# DRV10987.net
KiCad netlist of a schematic drawn in EAGLE
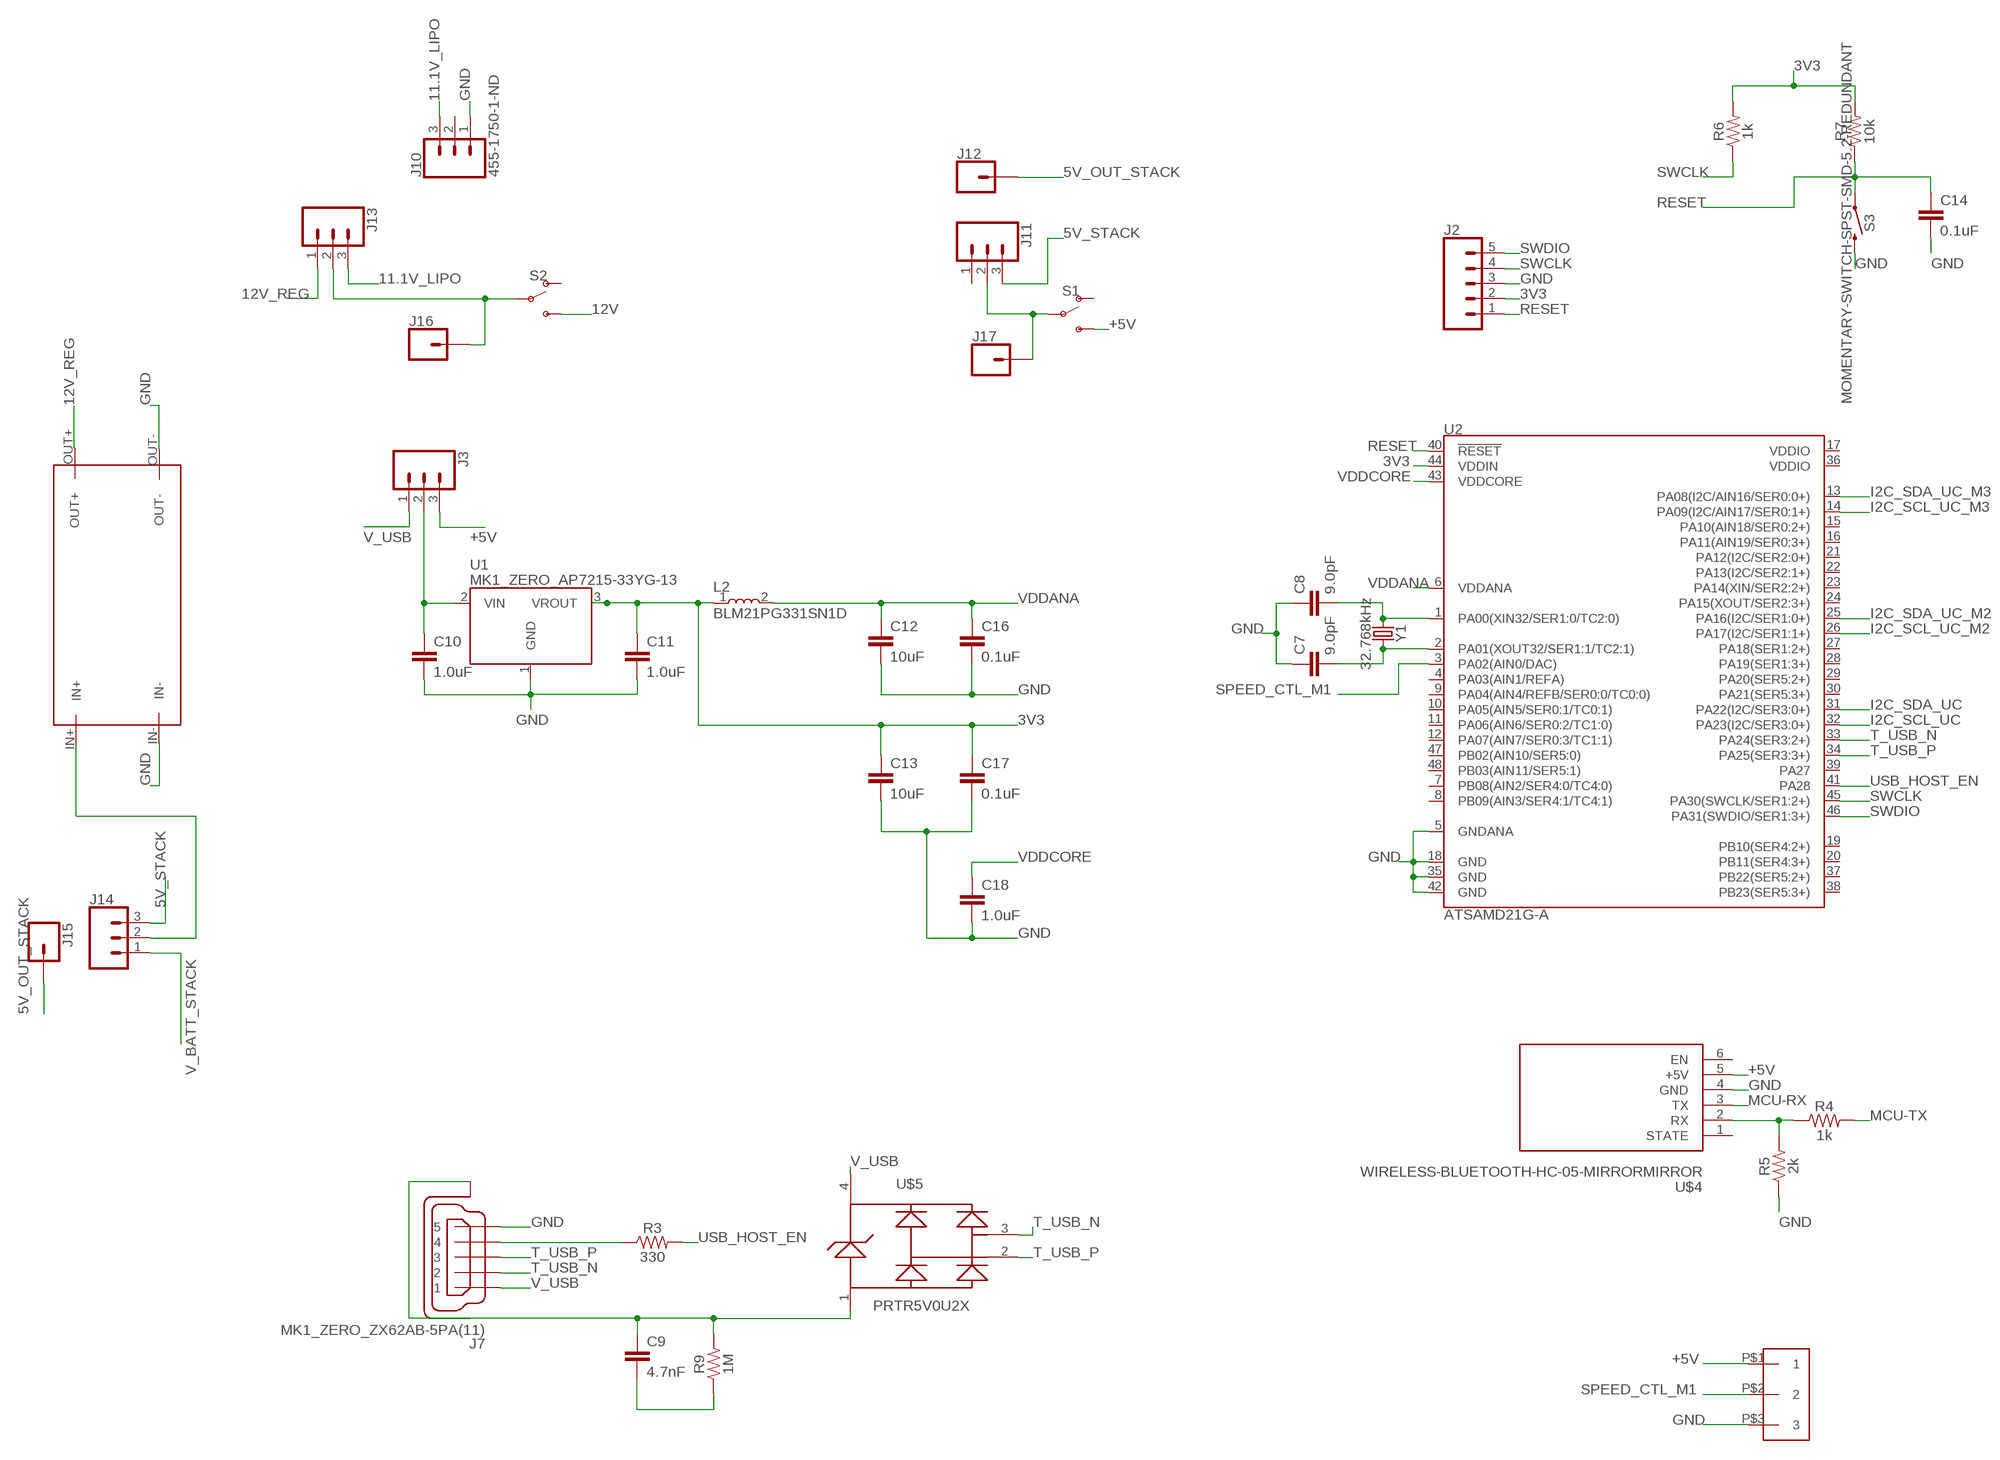
[diagram p0: schematic, sheet 1, part 1 of 2]
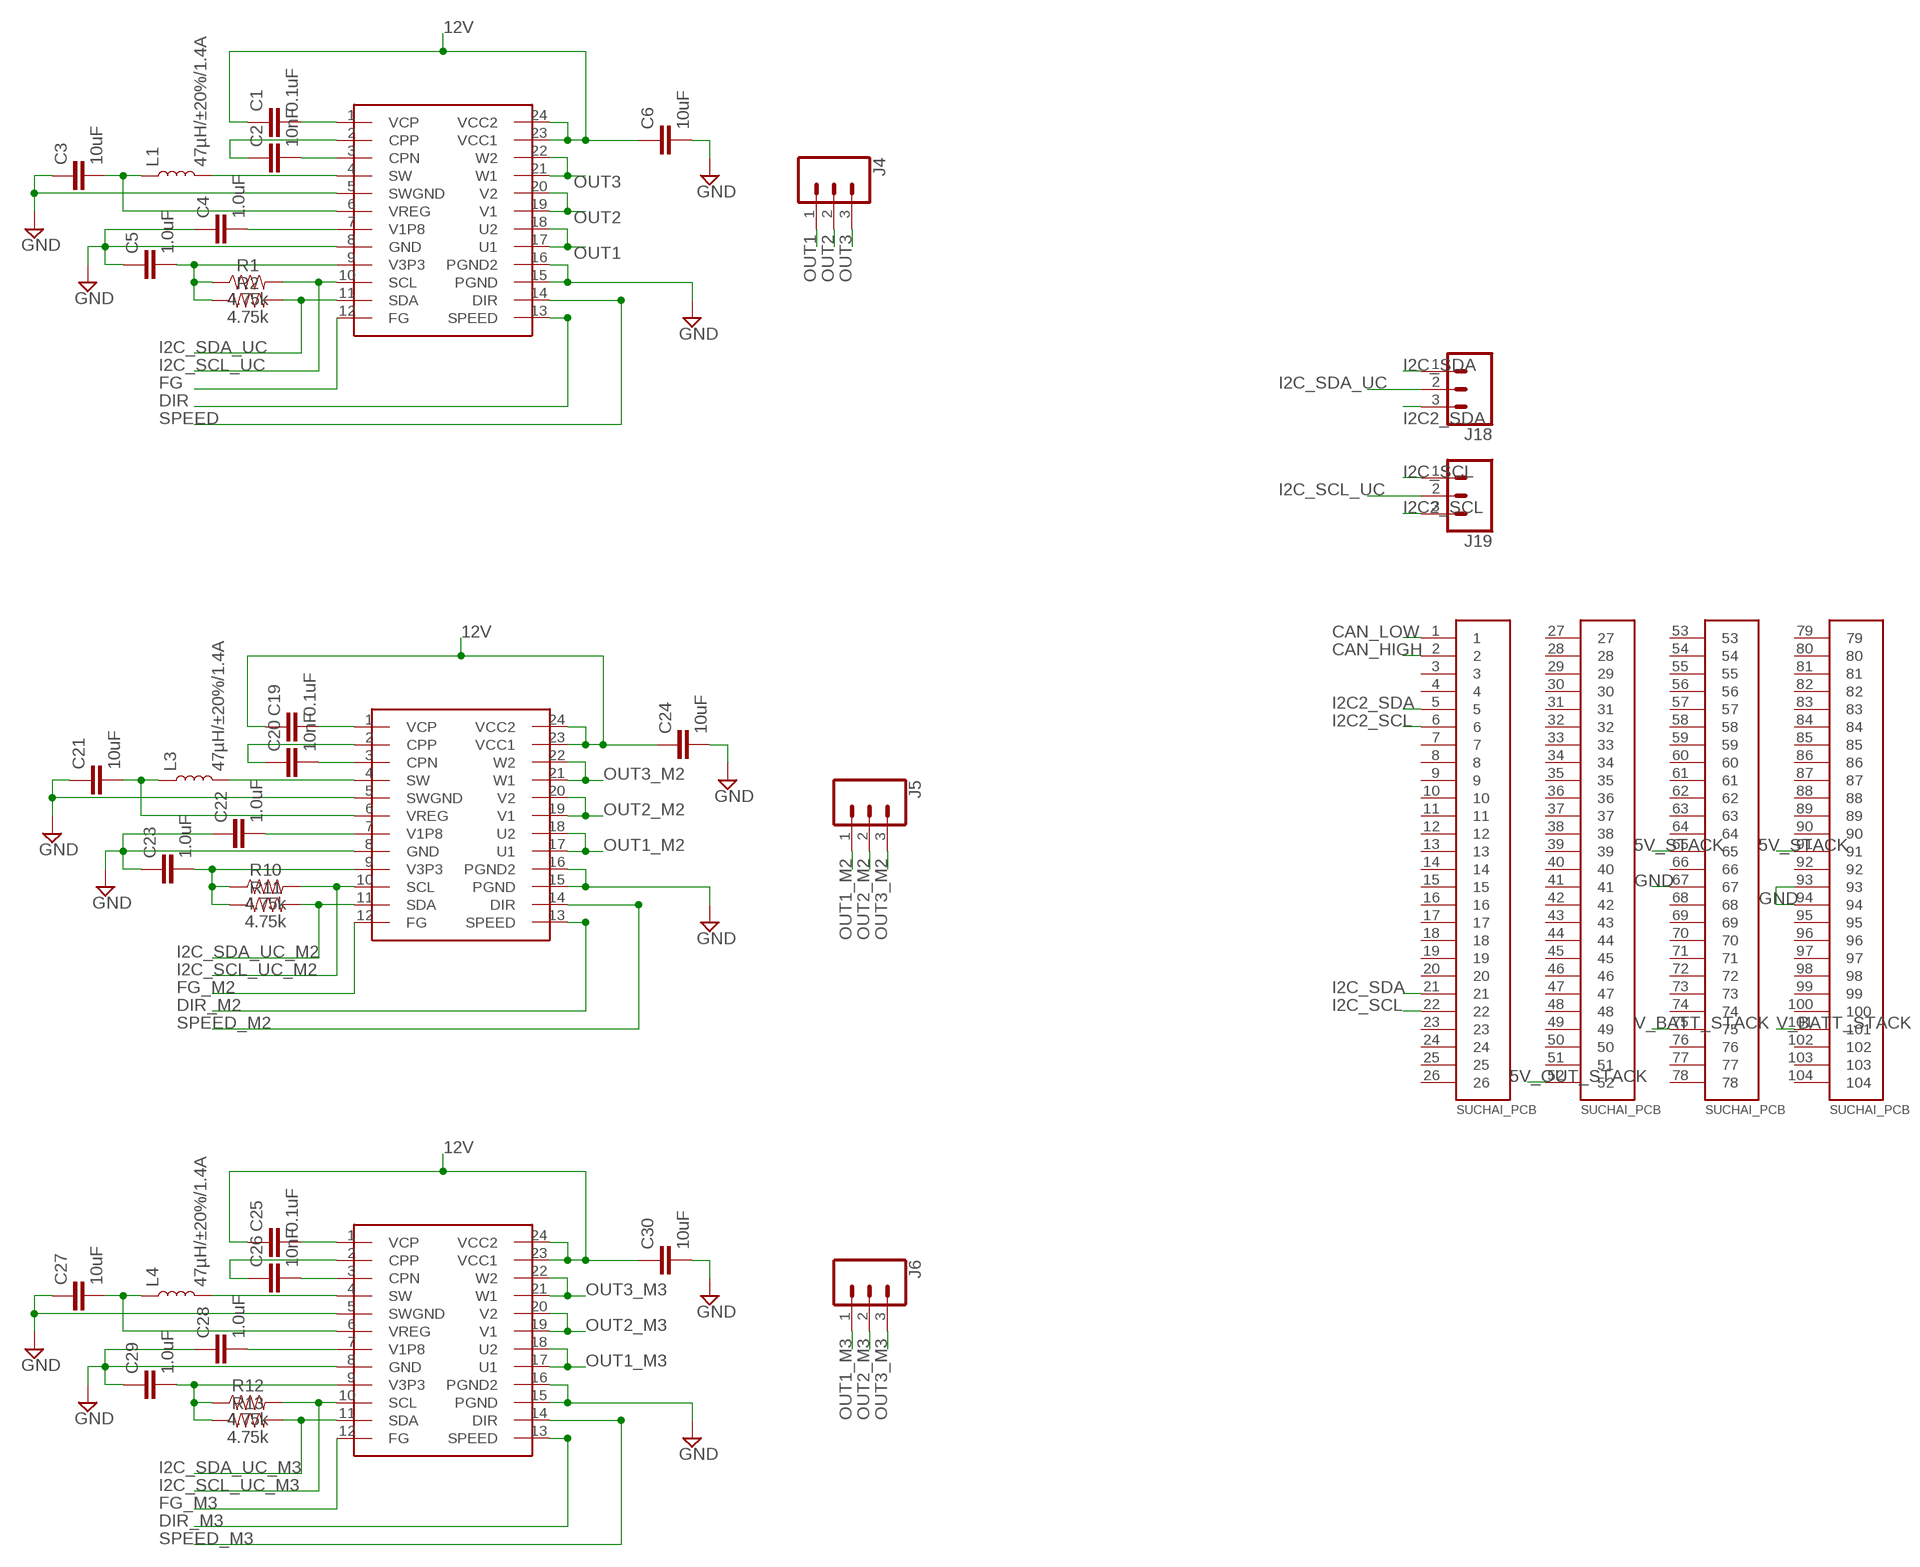
[diagram p1: schematic, sheet 1, part 2 of 2]

(export (version "E")
  (design (tool "Eeschema 10.0.6"))
  (components
    (comp (ref "C1")
      (value "0.1uF")
      (footprint "eagle-import:0805")
      (libsource (lib "eagle-import") (part "1.0UF-0805-25V-10%"))
    )
    (comp (ref "C2")
      (value "10nF")
      (footprint "eagle-import:0805")
      (libsource (lib "eagle-import") (part "1.0UF-0805-25V-10%"))
    )
    (comp (ref "C3")
      (value "10uF")
      (footprint "eagle-import:0805")
      (libsource (lib "eagle-import") (part "1.0UF-0805-25V-10%"))
    )
    (comp (ref "C4")
      (value "1.0uF")
      (footprint "eagle-import:0805")
      (libsource (lib "eagle-import") (part "1.0UF-0805-25V-10%"))
    )
    (comp (ref "C5")
      (value "1.0uF")
      (footprint "eagle-import:0805")
      (libsource (lib "eagle-import") (part "1.0UF-0805-25V-10%"))
    )
    (comp (ref "C6")
      (value "10uF")
      (footprint "eagle-import:0805")
      (libsource (lib "eagle-import") (part "1.0UF-0805-25V-10%"))
    )
    (comp (ref "C7")
      (value "9.0pF")
      (footprint "eagle-import:0603")
      (libsource (lib "eagle-import") (part "9.0PF-0603-50V-10%"))
    )
    (comp (ref "C8")
      (value "9.0pF")
      (footprint "eagle-import:0603")
      (libsource (lib "eagle-import") (part "9.0PF-0603-50V-10%"))
    )
    (comp (ref "C9")
      (value "4.7nF")
      (footprint "eagle-import:0603")
      (libsource (lib "eagle-import") (part "4.7PF-0603-50V-5%"))
    )
    (comp (ref "C10")
      (value "1.0uF")
      (footprint "eagle-import:0805")
      (libsource (lib "eagle-import") (part "1.0UF-0805-25V-(+80/-20%)"))
    )
    (comp (ref "C11")
      (value "1.0uF")
      (footprint "eagle-import:0805")
      (libsource (lib "eagle-import") (part "1.0UF-0805-25V-(+80/-20%)"))
    )
    (comp (ref "C12")
      (value "10uF")
      (footprint "eagle-import:0805")
      (libsource (lib "eagle-import") (part "10UF-0805-10V-10%"))
    )
    (comp (ref "C13")
      (value "10uF")
      (footprint "eagle-import:0805")
      (libsource (lib "eagle-import") (part "10UF-0805-10V-10%"))
    )
    (comp (ref "C14")
      (value "0.1uF")
      (footprint "eagle-import:0805")
      (libsource (lib "eagle-import") (part "1.0UF-0805-25V-(+80/-20%)"))
    )
    (comp (ref "C16")
      (value "0.1uF")
      (footprint "eagle-import:0805")
      (libsource (lib "eagle-import") (part "1.0UF-0805-25V-(+80/-20%)"))
    )
    (comp (ref "C17")
      (value "0.1uF")
      (footprint "eagle-import:0805")
      (libsource (lib "eagle-import") (part "1.0UF-0805-25V-(+80/-20%)"))
    )
    (comp (ref "C18")
      (value "1.0uF")
      (footprint "eagle-import:0805")
      (libsource (lib "eagle-import") (part "1.0UF-0805-25V-(+80/-20%)"))
    )
    (comp (ref "C19")
      (value "0.1uF")
      (footprint "eagle-import:0805")
      (libsource (lib "eagle-import") (part "1.0UF-0805-25V-10%"))
    )
    (comp (ref "C20")
      (value "10nF")
      (footprint "eagle-import:0805")
      (libsource (lib "eagle-import") (part "1.0UF-0805-25V-10%"))
    )
    (comp (ref "C21")
      (value "10uF")
      (footprint "eagle-import:0805")
      (libsource (lib "eagle-import") (part "1.0UF-0805-25V-10%"))
    )
    (comp (ref "C22")
      (value "1.0uF")
      (footprint "eagle-import:0805")
      (libsource (lib "eagle-import") (part "1.0UF-0805-25V-10%"))
    )
    (comp (ref "C23")
      (value "1.0uF")
      (footprint "eagle-import:0805")
      (libsource (lib "eagle-import") (part "1.0UF-0805-25V-10%"))
    )
    (comp (ref "C24")
      (value "10uF")
      (footprint "eagle-import:0805")
      (libsource (lib "eagle-import") (part "1.0UF-0805-25V-10%"))
    )
    (comp (ref "C25")
      (value "0.1uF")
      (footprint "eagle-import:0805")
      (libsource (lib "eagle-import") (part "1.0UF-0805-25V-10%"))
    )
    (comp (ref "C26")
      (value "10nF")
      (footprint "eagle-import:0805")
      (libsource (lib "eagle-import") (part "1.0UF-0805-25V-10%"))
    )
    (comp (ref "C27")
      (value "10uF")
      (footprint "eagle-import:0805")
      (libsource (lib "eagle-import") (part "1.0UF-0805-25V-10%"))
    )
    (comp (ref "C28")
      (value "1.0uF")
      (footprint "eagle-import:0805")
      (libsource (lib "eagle-import") (part "1.0UF-0805-25V-10%"))
    )
    (comp (ref "C29")
      (value "1.0uF")
      (footprint "eagle-import:0805")
      (libsource (lib "eagle-import") (part "1.0UF-0805-25V-10%"))
    )
    (comp (ref "C30")
      (value "10uF")
      (footprint "eagle-import:0805")
      (libsource (lib "eagle-import") (part "1.0UF-0805-25V-10%"))
    )
    (comp (ref "J1")
      (value "SUCHAI_PCB")
      (footprint "eagle-import:SUCHAI_PCB")
      (libsource (lib "eagle-import") (part "SUCHAI_PCB"))
    )
    (comp (ref "J2")
      (value "CONN_05LOCK_LONGPADS")
      (footprint "eagle-import:1X05_LOCK_LONGPADS")
      (libsource (lib "eagle-import") (part "CONN_05LOCK_LONGPADS"))
    )
    (comp (ref "J3")
      (value "CONN_03LOCK_LONGPADS")
      (footprint "eagle-import:1X03_LOCK_LONGPADS")
      (libsource (lib "eagle-import") (part "CONN_03LOCK_LONGPADS"))
    )
    (comp (ref "J4")
      (value "CONN_03LOCK")
      (footprint "eagle-import:1X03_LOCK")
      (libsource (lib "eagle-import") (part "CONN_03LOCK"))
    )
    (comp (ref "J5")
      (value "CONN_03LOCK")
      (footprint "eagle-import:1X03_LOCK")
      (libsource (lib "eagle-import") (part "CONN_03LOCK"))
    )
    (comp (ref "J6")
      (value "CONN_03LOCK")
      (footprint "eagle-import:1X03_LOCK")
      (libsource (lib "eagle-import") (part "CONN_03LOCK"))
    )
    (comp (ref "J7")
      (value "MK1_ZERO_ZX62AB-5PA(11)")
      (footprint "eagle-import:MK1_ZERO_USBMICRO-ZX62-AB-5PA")
      (libsource (lib "eagle-import") (part "MK1_ZERO_ZX62AB-5PA(11)"))
    )
    (comp (ref "J10")
      (value "455-1750-1-ND")
      (footprint "eagle-import:1X03")
      (libsource (lib "eagle-import") (part "CONN_03"))
    )
    (comp (ref "J11")
      (value "CONN_03LOCK")
      (footprint "eagle-import:1X03_LOCK")
      (libsource (lib "eagle-import") (part "CONN_03LOCK"))
    )
    (comp (ref "J12")
      (value "CONN_01")
      (footprint "eagle-import:1X01")
      (libsource (lib "eagle-import") (part "CONN_01"))
    )
    (comp (ref "J13")
      (value "CONN_03LOCK")
      (footprint "eagle-import:1X03_LOCK")
      (libsource (lib "eagle-import") (part "CONN_03LOCK"))
    )
    (comp (ref "J14")
      (value "CONN_03LOCK")
      (footprint "eagle-import:1X03_LOCK")
      (libsource (lib "eagle-import") (part "CONN_03LOCK"))
    )
    (comp (ref "J15")
      (value "CONN_01")
      (footprint "eagle-import:1X01")
      (libsource (lib "eagle-import") (part "CONN_01"))
    )
    (comp (ref "J16")
      (value "CONN_01")
      (footprint "eagle-import:1X01")
      (libsource (lib "eagle-import") (part "CONN_01"))
    )
    (comp (ref "J17")
      (value "CONN_01")
      (footprint "eagle-import:1X01")
      (libsource (lib "eagle-import") (part "CONN_01"))
    )
    (comp (ref "J18")
      (value "CONN_03LOCK")
      (footprint "eagle-import:1X03_LOCK")
      (libsource (lib "eagle-import") (part "CONN_03LOCK"))
    )
    (comp (ref "J19")
      (value "CONN_03LOCK")
      (footprint "eagle-import:1X03_LOCK")
      (libsource (lib "eagle-import") (part "CONN_03LOCK"))
    )
    (comp (ref "L1")
      (value "47µH/±20%/1.4A")
      (footprint "eagle-import:SRN6045")
      (libsource (lib "eagle-import") (part "INDUCTOR-SRN6045-33UH"))
    )
    (comp (ref "L2")
      (value "BLM21PG331SN1D")
      (footprint "eagle-import:INDC2012X87")
      (fields (field (name "MANUFACTURER") "MURATA"))
      (libsource (lib "eagle-import") (part "BLM21PG331SN1D"))
    )
    (comp (ref "L3")
      (value "47µH/±20%/1.4A")
      (footprint "eagle-import:SRN6045")
      (libsource (lib "eagle-import") (part "INDUCTOR-SRN6045-33UH"))
    )
    (comp (ref "L4")
      (value "47µH/±20%/1.4A")
      (footprint "eagle-import:SRN6045")
      (libsource (lib "eagle-import") (part "INDUCTOR-SRN6045-33UH"))
    )
    (comp (ref "R1")
      (value "4.75k")
      (footprint "eagle-import:0805")
      (libsource (lib "eagle-import") (part "RESISTOR0805"))
    )
    (comp (ref "R2")
      (value "4.75k")
      (footprint "eagle-import:0805")
      (libsource (lib "eagle-import") (part "RESISTOR0805"))
    )
    (comp (ref "R3")
      (value "330")
      (footprint "eagle-import:0603")
      (libsource (lib "eagle-import") (part "330OHM-0603-1/10W-1%"))
    )
    (comp (ref "R4")
      (value "1k")
      (footprint "eagle-import:AXIAL-0.3")
      (libsource (lib "eagle-import") (part "resistors-longpads_1KOHM-HORIZ-1/4W-5%"))
    )
    (comp (ref "R5")
      (value "2k")
      (footprint "eagle-import:AXIAL-0.3")
      (libsource (lib "eagle-import") (part "resistors-longpads_RESISTORAXIAL-0.3"))
    )
    (comp (ref "R6")
      (value "1k")
      (footprint "eagle-import:0603")
      (libsource (lib "eagle-import") (part "1KOHM-0603-1/10W-1%"))
    )
    (comp (ref "R7")
      (value "10k")
      (footprint "eagle-import:0603")
      (libsource (lib "eagle-import") (part "10KOHM-0603-1/10W-1%"))
    )
    (comp (ref "R9")
      (value "1M")
      (footprint "eagle-import:0603")
      (libsource (lib "eagle-import") (part "1MOHM-0603-1/4W-5%"))
    )
    (comp (ref "R10")
      (value "4.75k")
      (footprint "eagle-import:0805")
      (libsource (lib "eagle-import") (part "RESISTOR0805"))
    )
    (comp (ref "R11")
      (value "4.75k")
      (footprint "eagle-import:0805")
      (libsource (lib "eagle-import") (part "RESISTOR0805"))
    )
    (comp (ref "R12")
      (value "4.75k")
      (footprint "eagle-import:0805")
      (libsource (lib "eagle-import") (part "RESISTOR0805"))
    )
    (comp (ref "R13")
      (value "4.75k")
      (footprint "eagle-import:0805")
      (libsource (lib "eagle-import") (part "RESISTOR0805"))
    )
    (comp (ref "S1")
      (value "SWITCH-SPDT-PTH-11.6X4.0MM")
      (footprint "eagle-import:SWITCH_SPDT_PTH_11.6X4.0MM")
      (libsource (lib "eagle-import") (part "SWITCH-SPDT-PTH-11.6X4.0MM"))
    )
    (comp (ref "S2")
      (value "SWITCH-SPDT-PTH-11.6X4.0MM")
      (footprint "eagle-import:SWITCH_SPDT_PTH_11.6X4.0MM")
      (libsource (lib "eagle-import") (part "SWITCH-SPDT-PTH-11.6X4.0MM"))
    )
    (comp (ref "S3")
      (value "MOMENTARY-SWITCH-SPST-SMD-5.2-REDUNDANT")
      (footprint "eagle-import:TACTILE_SWITCH_SMD_5.2MM")
      (libsource (lib "eagle-import") (part "MOMENTARY-SWITCH-SPST-SMD-5.2-REDUNDANT"))
    )
    (comp (ref "U$1")
      (value "DRV10987")
      (footprint "eagle-import:DRV10987")
      (libsource (lib "eagle-import") (part "DRV10987"))
    )
    (comp (ref "U$2")
      (value "XL6009E1_MODULE")
      (footprint "eagle-import:XL6009E1_MODULE")
      (libsource (lib "eagle-import") (part "XL6009E1_MODULE"))
    )
    (comp (ref "U$3")
      (value "CONN_03_SMD_SMALL")
      (footprint "eagle-import:CONN_03_SMD_SMALL")
      (libsource (lib "eagle-import") (part "CONN_03_SMD_SMALL"))
    )
    (comp (ref "U$4")
      (value "WIRELESS-BLUETOOTH-HC-05-MIRRORMIRROR")
      (footprint "eagle-import:WIRELESS-BLUETOOTH-HC-05-MIRROR")
      (libsource (lib "eagle-import") (part "WIRELESS-BLUETOOTH-HC-05-MIRRORMIRROR"))
    )
    (comp (ref "U$5")
      (value "ARDUINO_PRTR5V0U2XB")
      (footprint "eagle-import:ARDUINO_SOT143B")
      (libsource (lib "eagle-import") (part "ARDUINO_PRTR5V0U2XB"))
    )
    (comp (ref "U$6")
      (value "DRV10987")
      (footprint "eagle-import:DRV10987")
      (libsource (lib "eagle-import") (part "DRV10987"))
    )
    (comp (ref "U$7")
      (value "DRV10987")
      (footprint "eagle-import:DRV10987")
      (libsource (lib "eagle-import") (part "DRV10987"))
    )
    (comp (ref "U1")
      (value "MK1_ZERO_AP7215-33YG-13")
      (footprint "eagle-import:MK1_ZERO_SOT150P400X160-3N")
      (fields (field (name "MF") "Diodes Inc ") (field (name "MPN") "AP7215-33YG-13 "))
      (libsource (lib "eagle-import") (part "MK1_ZERO_AP7215-33YG-13"))
    )
    (comp (ref "U2")
      (value "ATSAMD21G-A")
      (footprint "eagle-import:TQFP-48")
      (libsource (lib "eagle-import") (part "ATSAMD21G-A"))
    )
    (comp (ref "Y1")
      (value "32.768kHz")
      (footprint "eagle-import:CRYSTAL-SMD-3.2X1.5MM")
      (libsource (lib "eagle-import") (part "CRYSTAL-32.768KHZSMD-3.2X1.5"))
    )
  )
  (nets
    (net (code "1") (name "/+5V") (class "Default")
      (node (ref "J3") (pin "3") (pinfunction "3_3") (pintype "passive"))
      (node (ref "S1") (pin "3") (pinfunction "S_3") (pintype "passive"))
      (node (ref "U$3") (pin "P$1") (pinfunction "1_P$1") (pintype "bidirectional"))
      (node (ref "U$4") (pin "5") (pinfunction "+5V_5") (pintype "power_in"))
    )
    (net (code "2") (name "/3V3") (class "Default")
      (node (ref "C11") (pin "1") (pinfunction "1_1") (pintype "passive"))
      (node (ref "C13") (pin "1") (pinfunction "1_1") (pintype "passive"))
      (node (ref "C17") (pin "1") (pinfunction "1_1") (pintype "passive"))
      (node (ref "J2") (pin "2") (pinfunction "2_2") (pintype "passive"))
      (node (ref "L2") (pin "1") (pinfunction "1_1") (pintype "passive"))
      (node (ref "R6") (pin "2") (pinfunction "2_2") (pintype "passive"))
      (node (ref "R7") (pin "2") (pinfunction "2_2") (pintype "passive"))
      (node (ref "U1") (pin "3") (pinfunction "VROUT_3") (pintype "power_in"))
      (node (ref "U2") (pin "44") (pinfunction "VDDIN_44") (pintype "bidirectional"))
    )
    (net (code "3") (name "/5V_OUT_STACK") (class "Default")
      (node (ref "J1") (pin "52") (pinfunction "52_52") (pintype "bidirectional"))
      (node (ref "J12") (pin "1") (pinfunction "1_1") (pintype "passive"))
      (node (ref "J15") (pin "1") (pinfunction "1_1") (pintype "passive"))
    )
    (net (code "4") (name "/5V_STACK") (class "Default")
      (node (ref "J1") (pin "65") (pinfunction "65_65") (pintype "bidirectional"))
      (node (ref "J1") (pin "91") (pinfunction "91_91") (pintype "bidirectional"))
      (node (ref "J11") (pin "3") (pinfunction "3_3") (pintype "passive"))
      (node (ref "J14") (pin "3") (pinfunction "3_3") (pintype "passive"))
    )
    (net (code "5") (name "/11.1V_LIPO") (class "Default")
      (node (ref "J10") (pin "3") (pinfunction "3_3") (pintype "passive"))
      (node (ref "J13") (pin "3") (pinfunction "3_3") (pintype "passive"))
    )
    (net (code "6") (name "/12V") (class "Default")
      (node (ref "C1") (pin "1") (pinfunction "1_1") (pintype "passive"))
      (node (ref "C19") (pin "1") (pinfunction "1_1") (pintype "passive"))
      (node (ref "C24") (pin "1") (pinfunction "1_1") (pintype "passive"))
      (node (ref "C25") (pin "1") (pinfunction "1_1") (pintype "passive"))
      (node (ref "C30") (pin "1") (pinfunction "1_1") (pintype "passive"))
      (node (ref "C6") (pin "1") (pinfunction "1_1") (pintype "passive"))
      (node (ref "S2") (pin "3") (pinfunction "S_3") (pintype "passive"))
      (node (ref "U$1") (pin "23") (pinfunction "VCC1_23") (pintype "bidirectional"))
      (node (ref "U$1") (pin "24") (pinfunction "VCC2_24") (pintype "bidirectional"))
      (node (ref "U$6") (pin "23") (pinfunction "VCC1_23") (pintype "bidirectional"))
      (node (ref "U$6") (pin "24") (pinfunction "VCC2_24") (pintype "bidirectional"))
      (node (ref "U$7") (pin "23") (pinfunction "VCC1_23") (pintype "bidirectional"))
      (node (ref "U$7") (pin "24") (pinfunction "VCC2_24") (pintype "bidirectional"))
    )
    (net (code "7") (name "/12V_REG") (class "Default")
      (node (ref "J13") (pin "1") (pinfunction "1_1") (pintype "passive"))
      (node (ref "U$2") (pin "OUT+") (pinfunction "OUT+_OUT+") (pintype "bidirectional"))
    )
    (net (code "8") (name "/CAN_HIGH") (class "Default")
      (node (ref "J1") (pin "2") (pinfunction "2_2") (pintype "bidirectional"))
    )
    (net (code "9") (name "/CAN_LOW") (class "Default")
      (node (ref "J1") (pin "1") (pinfunction "1_1") (pintype "bidirectional"))
    )
    (net (code "10") (name "/DIR") (class "Default")
      (node (ref "U$1") (pin "13") (pinfunction "SPEED_13") (pintype "bidirectional"))
    )
    (net (code "11") (name "/DIR_M2") (class "Default")
      (node (ref "U$6") (pin "13") (pinfunction "SPEED_13") (pintype "bidirectional"))
    )
    (net (code "12") (name "/DIR_M3") (class "Default")
      (node (ref "U$7") (pin "13") (pinfunction "SPEED_13") (pintype "bidirectional"))
    )
    (net (code "13") (name "/FG") (class "Default")
      (node (ref "U$1") (pin "12") (pinfunction "FG_12") (pintype "bidirectional"))
    )
    (net (code "14") (name "/FG_M2") (class "Default")
      (node (ref "U$6") (pin "12") (pinfunction "FG_12") (pintype "bidirectional"))
    )
    (net (code "15") (name "/FG_M3") (class "Default")
      (node (ref "U$7") (pin "12") (pinfunction "FG_12") (pintype "bidirectional"))
    )
    (net (code "16") (name "/I2C2_SCL") (class "Default")
      (node (ref "J1") (pin "6") (pinfunction "6_6") (pintype "bidirectional"))
      (node (ref "J19") (pin "3") (pinfunction "3_3") (pintype "passive"))
    )
    (net (code "17") (name "/I2C2_SDA") (class "Default")
      (node (ref "J1") (pin "5") (pinfunction "5_5") (pintype "bidirectional"))
      (node (ref "J18") (pin "3") (pinfunction "3_3") (pintype "passive"))
    )
    (net (code "18") (name "/I2C_SCL") (class "Default")
      (node (ref "J1") (pin "22") (pinfunction "22_22") (pintype "bidirectional"))
      (node (ref "J19") (pin "1") (pinfunction "1_1") (pintype "passive"))
    )
    (net (code "19") (name "/I2C_SCL_UC") (class "Default")
      (node (ref "J19") (pin "2") (pinfunction "2_2") (pintype "passive"))
      (node (ref "R1") (pin "2") (pinfunction "2_2") (pintype "passive"))
      (node (ref "U$1") (pin "10") (pinfunction "SCL_10") (pintype "bidirectional"))
      (node (ref "U2") (pin "32") (pinfunction "PA23(I2C/SER3:0+)_32") (pintype "bidirectional"))
    )
    (net (code "20") (name "/I2C_SCL_UC_M2") (class "Default")
      (node (ref "R10") (pin "2") (pinfunction "2_2") (pintype "passive"))
      (node (ref "U$6") (pin "10") (pinfunction "SCL_10") (pintype "bidirectional"))
      (node (ref "U2") (pin "26") (pinfunction "PA17(I2C/SER1:1+)_26") (pintype "bidirectional"))
    )
    (net (code "21") (name "/I2C_SCL_UC_M3") (class "Default")
      (node (ref "R12") (pin "2") (pinfunction "2_2") (pintype "passive"))
      (node (ref "U$7") (pin "10") (pinfunction "SCL_10") (pintype "bidirectional"))
      (node (ref "U2") (pin "14") (pinfunction "PA09(I2C/AIN17/SER0:1+)_14") (pintype "bidirectional"))
    )
    (net (code "22") (name "/I2C_SDA") (class "Default")
      (node (ref "J1") (pin "21") (pinfunction "21_21") (pintype "bidirectional"))
      (node (ref "J18") (pin "1") (pinfunction "1_1") (pintype "passive"))
    )
    (net (code "23") (name "/I2C_SDA_UC") (class "Default")
      (node (ref "J18") (pin "2") (pinfunction "2_2") (pintype "passive"))
      (node (ref "R2") (pin "2") (pinfunction "2_2") (pintype "passive"))
      (node (ref "U$1") (pin "11") (pinfunction "SDA_11") (pintype "bidirectional"))
      (node (ref "U2") (pin "31") (pinfunction "PA22(I2C/SER3:0+)_31") (pintype "bidirectional"))
    )
    (net (code "24") (name "/I2C_SDA_UC_M2") (class "Default")
      (node (ref "R11") (pin "2") (pinfunction "2_2") (pintype "passive"))
      (node (ref "U$6") (pin "11") (pinfunction "SDA_11") (pintype "bidirectional"))
      (node (ref "U2") (pin "25") (pinfunction "PA16(I2C/SER1:0+)_25") (pintype "bidirectional"))
    )
    (net (code "25") (name "/I2C_SDA_UC_M3") (class "Default")
      (node (ref "R13") (pin "2") (pinfunction "2_2") (pintype "passive"))
      (node (ref "U$7") (pin "11") (pinfunction "SDA_11") (pintype "bidirectional"))
      (node (ref "U2") (pin "13") (pinfunction "PA08(I2C/AIN16/SER0:0+)_13") (pintype "bidirectional"))
    )
    (net (code "26") (name "/MCU-RX") (class "Default")
      (node (ref "U$4") (pin "3") (pinfunction "TX_3") (pintype "bidirectional"))
    )
    (net (code "27") (name "/MCU-TX") (class "Default")
      (node (ref "R4") (pin "P$2") (pinfunction "2_P$2") (pintype "passive"))
    )
    (net (code "28") (name "/OUT1") (class "Default")
      (node (ref "J4") (pin "1") (pinfunction "1_1") (pintype "passive"))
      (node (ref "U$1") (pin "17") (pinfunction "U1_17") (pintype "bidirectional"))
      (node (ref "U$1") (pin "18") (pinfunction "U2_18") (pintype "bidirectional"))
    )
    (net (code "29") (name "/OUT1_M2") (class "Default")
      (node (ref "J5") (pin "1") (pinfunction "1_1") (pintype "passive"))
      (node (ref "U$6") (pin "17") (pinfunction "U1_17") (pintype "bidirectional"))
      (node (ref "U$6") (pin "18") (pinfunction "U2_18") (pintype "bidirectional"))
    )
    (net (code "30") (name "/OUT1_M3") (class "Default")
      (node (ref "J6") (pin "1") (pinfunction "1_1") (pintype "passive"))
      (node (ref "U$7") (pin "17") (pinfunction "U1_17") (pintype "bidirectional"))
      (node (ref "U$7") (pin "18") (pinfunction "U2_18") (pintype "bidirectional"))
    )
    (net (code "31") (name "/OUT2") (class "Default")
      (node (ref "J4") (pin "2") (pinfunction "2_2") (pintype "passive"))
      (node (ref "U$1") (pin "19") (pinfunction "V1_19") (pintype "bidirectional"))
      (node (ref "U$1") (pin "20") (pinfunction "V2_20") (pintype "bidirectional"))
    )
    (net (code "32") (name "/OUT2_M2") (class "Default")
      (node (ref "J5") (pin "2") (pinfunction "2_2") (pintype "passive"))
      (node (ref "U$6") (pin "19") (pinfunction "V1_19") (pintype "bidirectional"))
      (node (ref "U$6") (pin "20") (pinfunction "V2_20") (pintype "bidirectional"))
    )
    (net (code "33") (name "/OUT2_M3") (class "Default")
      (node (ref "J6") (pin "2") (pinfunction "2_2") (pintype "passive"))
      (node (ref "U$7") (pin "19") (pinfunction "V1_19") (pintype "bidirectional"))
      (node (ref "U$7") (pin "20") (pinfunction "V2_20") (pintype "bidirectional"))
    )
    (net (code "34") (name "/OUT3") (class "Default")
      (node (ref "J4") (pin "3") (pinfunction "3_3") (pintype "passive"))
      (node (ref "U$1") (pin "21") (pinfunction "W1_21") (pintype "bidirectional"))
      (node (ref "U$1") (pin "22") (pinfunction "W2_22") (pintype "bidirectional"))
    )
    (net (code "35") (name "/OUT3_M2") (class "Default")
      (node (ref "J5") (pin "3") (pinfunction "3_3") (pintype "passive"))
      (node (ref "U$6") (pin "21") (pinfunction "W1_21") (pintype "bidirectional"))
      (node (ref "U$6") (pin "22") (pinfunction "W2_22") (pintype "bidirectional"))
    )
    (net (code "36") (name "/OUT3_M3") (class "Default")
      (node (ref "J6") (pin "3") (pinfunction "3_3") (pintype "passive"))
      (node (ref "U$7") (pin "21") (pinfunction "W1_21") (pintype "bidirectional"))
      (node (ref "U$7") (pin "22") (pinfunction "W2_22") (pintype "bidirectional"))
    )
    (net (code "37") (name "/RESET") (class "Default")
      (node (ref "C14") (pin "1") (pinfunction "1_1") (pintype "passive"))
      (node (ref "J2") (pin "1") (pinfunction "1_1") (pintype "passive"))
      (node (ref "R7") (pin "1") (pinfunction "1_1") (pintype "passive"))
      (node (ref "S3") (pin "1") (pinfunction "1_1") (pintype "passive"))
      (node (ref "S3") (pin "2") (pinfunction "1_2") (pintype "passive"))
      (node (ref "U2") (pin "40") (pinfunction "~{RESET}_40") (pintype "bidirectional"))
    )
    (net (code "38") (name "/SPEED") (class "Default")
      (node (ref "U$1") (pin "14") (pinfunction "DIR_14") (pintype "bidirectional"))
    )
    (net (code "39") (name "/SPEED_CTL_M1") (class "Default")
      (node (ref "U$3") (pin "P$2") (pinfunction "2_P$2") (pintype "bidirectional"))
      (node (ref "U2") (pin "3") (pinfunction "PA02(AIN0/DAC)_3") (pintype "bidirectional"))
    )
    (net (code "40") (name "/SPEED_M2") (class "Default")
      (node (ref "U$6") (pin "14") (pinfunction "DIR_14") (pintype "bidirectional"))
    )
    (net (code "41") (name "/SPEED_M3") (class "Default")
      (node (ref "U$7") (pin "14") (pinfunction "DIR_14") (pintype "bidirectional"))
    )
    (net (code "42") (name "/SWCLK") (class "Default")
      (node (ref "J2") (pin "4") (pinfunction "4_4") (pintype "passive"))
      (node (ref "R6") (pin "1") (pinfunction "1_1") (pintype "passive"))
      (node (ref "U2") (pin "45") (pinfunction "PA30(SWCLK/SER1:2+)_45") (pintype "bidirectional"))
    )
    (net (code "43") (name "/SWDIO") (class "Default")
      (node (ref "J2") (pin "5") (pinfunction "5_5") (pintype "passive"))
      (node (ref "U2") (pin "46") (pinfunction "PA31(SWDIO/SER1:3+)_46") (pintype "bidirectional"))
    )
    (net (code "44") (name "/T_USB_N") (class "Default")
      (node (ref "J7") (pin "2") (pinfunction "2_2") (pintype "passive"))
      (node (ref "U$5") (pin "3") (pinfunction "3_3") (pintype "bidirectional"))
      (node (ref "U2") (pin "33") (pinfunction "PA24(SER3:2+)_33") (pintype "bidirectional"))
    )
    (net (code "45") (name "/T_USB_P") (class "Default")
      (node (ref "J7") (pin "3") (pinfunction "3_3") (pintype "passive"))
      (node (ref "U$5") (pin "2") (pinfunction "2_2") (pintype "bidirectional"))
      (node (ref "U2") (pin "34") (pinfunction "PA25(SER3:3+)_34") (pintype "bidirectional"))
    )
    (net (code "46") (name "/USB_HOST_EN") (class "Default")
      (node (ref "R3") (pin "2") (pinfunction "2_2") (pintype "passive"))
      (node (ref "U2") (pin "41") (pinfunction "PA28_41") (pintype "bidirectional"))
    )
    (net (code "47") (name "/VDDANA") (class "Default")
      (node (ref "C12") (pin "1") (pinfunction "1_1") (pintype "passive"))
      (node (ref "C16") (pin "1") (pinfunction "1_1") (pintype "passive"))
      (node (ref "L2") (pin "2") (pinfunction "2_2") (pintype "passive"))
      (node (ref "U2") (pin "6") (pinfunction "VDDANA_6") (pintype "bidirectional"))
    )
    (net (code "48") (name "/VDDCORE") (class "Default")
      (node (ref "C18") (pin "1") (pinfunction "1_1") (pintype "passive"))
      (node (ref "U2") (pin "43") (pinfunction "VDDCORE_43") (pintype "bidirectional"))
    )
    (net (code "49") (name "/V_BATT_STACK") (class "Default")
      (node (ref "J1") (pin "101") (pinfunction "101_101") (pintype "bidirectional"))
      (node (ref "J1") (pin "75") (pinfunction "75_75") (pintype "bidirectional"))
      (node (ref "J14") (pin "1") (pinfunction "1_1") (pintype "passive"))
    )
    (net (code "50") (name "/V_USB") (class "Default")
      (node (ref "J3") (pin "1") (pinfunction "1_1") (pintype "passive"))
      (node (ref "J7") (pin "1") (pinfunction "1_1") (pintype "passive"))
      (node (ref "U$5") (pin "4") (pinfunction "4_4") (pintype "bidirectional"))
    )
    (net (code "51") (name "GND") (class "Default")
      (node (ref "C10") (pin "2") (pinfunction "2_2") (pintype "passive"))
      (node (ref "C11") (pin "2") (pinfunction "2_2") (pintype "passive"))
      (node (ref "C12") (pin "2") (pinfunction "2_2") (pintype "passive"))
      (node (ref "C13") (pin "2") (pinfunction "2_2") (pintype "passive"))
      (node (ref "C14") (pin "2") (pinfunction "2_2") (pintype "passive"))
      (node (ref "C16") (pin "2") (pinfunction "2_2") (pintype "passive"))
      (node (ref "C17") (pin "2") (pinfunction "2_2") (pintype "passive"))
      (node (ref "C18") (pin "2") (pinfunction "2_2") (pintype "passive"))
      (node (ref "C21") (pin "1") (pinfunction "1_1") (pintype "passive"))
      (node (ref "C22") (pin "1") (pinfunction "1_1") (pintype "passive"))
      (node (ref "C23") (pin "1") (pinfunction "1_1") (pintype "passive"))
      (node (ref "C24") (pin "2") (pinfunction "2_2") (pintype "passive"))
      (node (ref "C27") (pin "1") (pinfunction "1_1") (pintype "passive"))
      (node (ref "C28") (pin "1") (pinfunction "1_1") (pintype "passive"))
      (node (ref "C29") (pin "1") (pinfunction "1_1") (pintype "passive"))
      (node (ref "C3") (pin "1") (pinfunction "1_1") (pintype "passive"))
      (node (ref "C30") (pin "2") (pinfunction "2_2") (pintype "passive"))
      (node (ref "C4") (pin "1") (pinfunction "1_1") (pintype "passive"))
      (node (ref "C5") (pin "1") (pinfunction "1_1") (pintype "passive"))
      (node (ref "C6") (pin "2") (pinfunction "2_2") (pintype "passive"))
      (node (ref "C7") (pin "1") (pinfunction "1_1") (pintype "passive"))
      (node (ref "C8") (pin "1") (pinfunction "1_1") (pintype "passive"))
      (node (ref "J1") (pin "67") (pinfunction "67_67") (pintype "bidirectional"))
      (node (ref "J1") (pin "93") (pinfunction "93_93") (pintype "bidirectional"))
      (node (ref "J1") (pin "94") (pinfunction "94_94") (pintype "bidirectional"))
      (node (ref "J10") (pin "1") (pinfunction "1_1") (pintype "passive"))
      (node (ref "J2") (pin "3") (pinfunction "3_3") (pintype "passive"))
      (node (ref "J7") (pin "5") (pinfunction "5_5") (pintype "passive"))
      (node (ref "R5") (pin "P$1") (pinfunction "1_P$1") (pintype "passive"))
      (node (ref "S3") (pin "3") (pinfunction "2_3") (pintype "passive"))
      (node (ref "S3") (pin "4") (pinfunction "2_4") (pintype "passive"))
      (node (ref "U$1") (pin "15") (pinfunction "PGND_15") (pintype "bidirectional"))
      (node (ref "U$1") (pin "16") (pinfunction "PGND2_16") (pintype "bidirectional"))
      (node (ref "U$1") (pin "5") (pinfunction "SWGND_5") (pintype "bidirectional"))
      (node (ref "U$1") (pin "8") (pinfunction "GND_8") (pintype "bidirectional"))
      (node (ref "U$2") (pin "IN-") (pinfunction "IN-_IN-") (pintype "bidirectional"))
      (node (ref "U$2") (pin "OUT-") (pinfunction "OUT-_OUT-") (pintype "bidirectional"))
      (node (ref "U$3") (pin "P$3") (pinfunction "3_P$3") (pintype "bidirectional"))
      (node (ref "U$4") (pin "4") (pinfunction "GND_4") (pintype "power_in"))
      (node (ref "U$6") (pin "15") (pinfunction "PGND_15") (pintype "bidirectional"))
      (node (ref "U$6") (pin "16") (pinfunction "PGND2_16") (pintype "bidirectional"))
      (node (ref "U$6") (pin "5") (pinfunction "SWGND_5") (pintype "bidirectional"))
      (node (ref "U$6") (pin "8") (pinfunction "GND_8") (pintype "bidirectional"))
      (node (ref "U$7") (pin "15") (pinfunction "PGND_15") (pintype "bidirectional"))
      (node (ref "U$7") (pin "16") (pinfunction "PGND2_16") (pintype "bidirectional"))
      (node (ref "U$7") (pin "5") (pinfunction "SWGND_5") (pintype "bidirectional"))
      (node (ref "U$7") (pin "8") (pinfunction "GND_8") (pintype "bidirectional"))
      (node (ref "U1") (pin "1") (pinfunction "GND_1") (pintype "power_in"))
      (node (ref "U2") (pin "18") (pinfunction "GND_18") (pintype "bidirectional"))
      (node (ref "U2") (pin "35") (pinfunction "GND_35") (pintype "bidirectional"))
      (node (ref "U2") (pin "42") (pinfunction "GND_42") (pintype "bidirectional"))
      (node (ref "U2") (pin "5") (pinfunction "GNDANA_5") (pintype "bidirectional"))
    )
    (net (code "52") (name "Net-(C9-Pad1)") (class "Default")
      (node (ref "C9") (pin "1") (pinfunction "1_1") (pintype "passive"))
      (node (ref "J7") (pin "10") (pinfunction "SH_10") (pintype "passive"))
      (node (ref "J7") (pin "11") (pinfunction "SH_11") (pintype "passive"))
      (node (ref "J7") (pin "6") (pinfunction "SH_6") (pintype "passive"))
      (node (ref "J7") (pin "7") (pinfunction "SH_7") (pintype "passive"))
      (node (ref "J7") (pin "8") (pinfunction "SH_8") (pintype "passive"))
      (node (ref "J7") (pin "9") (pinfunction "SH_9") (pintype "passive"))
      (node (ref "R9") (pin "2") (pinfunction "2_2") (pintype "passive"))
      (node (ref "U$5") (pin "1") (pinfunction "1_1") (pintype "bidirectional"))
    )
    (net (code "53") (name "Net-(C9-Pad2)") (class "Default")
      (node (ref "C9") (pin "2") (pinfunction "2_2") (pintype "passive"))
      (node (ref "R9") (pin "1") (pinfunction "1_1") (pintype "passive"))
    )
    (net (code "54") (name "Net-(J7-Pad4)") (class "Default")
      (node (ref "J7") (pin "4") (pinfunction "4_4") (pintype "passive"))
      (node (ref "R3") (pin "1") (pinfunction "1_1") (pintype "passive"))
    )
    (net (code "55") (name "Net-(J14-Pad2)") (class "Default")
      (node (ref "J14") (pin "2") (pinfunction "2_2") (pintype "passive"))
      (node (ref "U$2") (pin "IN+") (pinfunction "IN+_IN+") (pintype "bidirectional"))
    )
    (net (code "56") (name "Net-(R4-1)") (class "Default")
      (node (ref "R4") (pin "P$1") (pinfunction "1_P$1") (pintype "passive"))
      (node (ref "R5") (pin "P$2") (pinfunction "2_P$2") (pintype "passive"))
      (node (ref "U$4") (pin "2") (pinfunction "RX_2") (pintype "bidirectional"))
    )
    (net (code "57") (name "Net-(S1-P)") (class "Default")
      (node (ref "J11") (pin "2") (pinfunction "2_2") (pintype "passive"))
      (node (ref "J17") (pin "1") (pinfunction "1_1") (pintype "passive"))
      (node (ref "S1") (pin "2") (pinfunction "P_2") (pintype "passive"))
    )
    (net (code "58") (name "Net-(S2-P)") (class "Default")
      (node (ref "J13") (pin "2") (pinfunction "2_2") (pintype "passive"))
      (node (ref "J16") (pin "1") (pinfunction "1_1") (pintype "passive"))
      (node (ref "S2") (pin "2") (pinfunction "P_2") (pintype "passive"))
    )
    (net (code "59") (name "Net-(U$1-CPN)") (class "Default")
      (node (ref "C2") (pin "2") (pinfunction "2_2") (pintype "passive"))
      (node (ref "U$1") (pin "3") (pinfunction "CPN_3") (pintype "bidirectional"))
    )
    (net (code "60") (name "Net-(U$1-CPP)") (class "Default")
      (node (ref "C2") (pin "1") (pinfunction "1_1") (pintype "passive"))
      (node (ref "U$1") (pin "2") (pinfunction "CPP_2") (pintype "bidirectional"))
    )
    (net (code "61") (name "Net-(U$1-SW)") (class "Default")
      (node (ref "L1") (pin "2") (pinfunction "2_2") (pintype "passive"))
      (node (ref "U$1") (pin "4") (pinfunction "SW_4") (pintype "bidirectional"))
    )
    (net (code "62") (name "Net-(U$1-V1P8)") (class "Default")
      (node (ref "C4") (pin "2") (pinfunction "2_2") (pintype "passive"))
      (node (ref "U$1") (pin "7") (pinfunction "V1P8_7") (pintype "bidirectional"))
    )
    (net (code "63") (name "Net-(U$1-V3P3)") (class "Default")
      (node (ref "C5") (pin "2") (pinfunction "2_2") (pintype "passive"))
      (node (ref "R1") (pin "1") (pinfunction "1_1") (pintype "passive"))
      (node (ref "R2") (pin "1") (pinfunction "1_1") (pintype "passive"))
      (node (ref "U$1") (pin "9") (pinfunction "V3P3_9") (pintype "bidirectional"))
    )
    (net (code "64") (name "Net-(U$1-VCP)") (class "Default")
      (node (ref "C1") (pin "2") (pinfunction "2_2") (pintype "passive"))
      (node (ref "U$1") (pin "1") (pinfunction "VCP_1") (pintype "bidirectional"))
    )
    (net (code "65") (name "Net-(U$1-VREG)") (class "Default")
      (node (ref "C3") (pin "2") (pinfunction "2_2") (pintype "passive"))
      (node (ref "L1") (pin "1") (pinfunction "1_1") (pintype "passive"))
      (node (ref "U$1") (pin "6") (pinfunction "VREG_6") (pintype "bidirectional"))
    )
    (net (code "66") (name "Net-(U$6-CPN)") (class "Default")
      (node (ref "C20") (pin "2") (pinfunction "2_2") (pintype "passive"))
      (node (ref "U$6") (pin "3") (pinfunction "CPN_3") (pintype "bidirectional"))
    )
    (net (code "67") (name "Net-(U$6-CPP)") (class "Default")
      (node (ref "C20") (pin "1") (pinfunction "1_1") (pintype "passive"))
      (node (ref "U$6") (pin "2") (pinfunction "CPP_2") (pintype "bidirectional"))
    )
    (net (code "68") (name "Net-(U$6-SW)") (class "Default")
      (node (ref "L3") (pin "2") (pinfunction "2_2") (pintype "passive"))
      (node (ref "U$6") (pin "4") (pinfunction "SW_4") (pintype "bidirectional"))
    )
    (net (code "69") (name "Net-(U$6-V1P8)") (class "Default")
      (node (ref "C22") (pin "2") (pinfunction "2_2") (pintype "passive"))
      (node (ref "U$6") (pin "7") (pinfunction "V1P8_7") (pintype "bidirectional"))
    )
    (net (code "70") (name "Net-(U$6-V3P3)") (class "Default")
      (node (ref "C23") (pin "2") (pinfunction "2_2") (pintype "passive"))
      (node (ref "R10") (pin "1") (pinfunction "1_1") (pintype "passive"))
      (node (ref "R11") (pin "1") (pinfunction "1_1") (pintype "passive"))
      (node (ref "U$6") (pin "9") (pinfunction "V3P3_9") (pintype "bidirectional"))
    )
    (net (code "71") (name "Net-(U$6-VCP)") (class "Default")
      (node (ref "C19") (pin "2") (pinfunction "2_2") (pintype "passive"))
      (node (ref "U$6") (pin "1") (pinfunction "VCP_1") (pintype "bidirectional"))
    )
    (net (code "72") (name "Net-(U$6-VREG)") (class "Default")
      (node (ref "C21") (pin "2") (pinfunction "2_2") (pintype "passive"))
      (node (ref "L3") (pin "1") (pinfunction "1_1") (pintype "passive"))
      (node (ref "U$6") (pin "6") (pinfunction "VREG_6") (pintype "bidirectional"))
    )
    (net (code "73") (name "Net-(U$7-CPN)") (class "Default")
      (node (ref "C26") (pin "2") (pinfunction "2_2") (pintype "passive"))
      (node (ref "U$7") (pin "3") (pinfunction "CPN_3") (pintype "bidirectional"))
    )
    (net (code "74") (name "Net-(U$7-CPP)") (class "Default")
      (node (ref "C26") (pin "1") (pinfunction "1_1") (pintype "passive"))
      (node (ref "U$7") (pin "2") (pinfunction "CPP_2") (pintype "bidirectional"))
    )
    (net (code "75") (name "Net-(U$7-SW)") (class "Default")
      (node (ref "L4") (pin "2") (pinfunction "2_2") (pintype "passive"))
      (node (ref "U$7") (pin "4") (pinfunction "SW_4") (pintype "bidirectional"))
    )
    (net (code "76") (name "Net-(U$7-V1P8)") (class "Default")
      (node (ref "C28") (pin "2") (pinfunction "2_2") (pintype "passive"))
      (node (ref "U$7") (pin "7") (pinfunction "V1P8_7") (pintype "bidirectional"))
    )
    (net (code "77") (name "Net-(U$7-V3P3)") (class "Default")
      (node (ref "C29") (pin "2") (pinfunction "2_2") (pintype "passive"))
      (node (ref "R12") (pin "1") (pinfunction "1_1") (pintype "passive"))
      (node (ref "R13") (pin "1") (pinfunction "1_1") (pintype "passive"))
      (node (ref "U$7") (pin "9") (pinfunction "V3P3_9") (pintype "bidirectional"))
    )
    (net (code "78") (name "Net-(U$7-VCP)") (class "Default")
      (node (ref "C25") (pin "2") (pinfunction "2_2") (pintype "passive"))
      (node (ref "U$7") (pin "1") (pinfunction "VCP_1") (pintype "bidirectional"))
    )
    (net (code "79") (name "Net-(U$7-VREG)") (class "Default")
      (node (ref "C27") (pin "2") (pinfunction "2_2") (pintype "passive"))
      (node (ref "L4") (pin "1") (pinfunction "1_1") (pintype "passive"))
      (node (ref "U$7") (pin "6") (pinfunction "VREG_6") (pintype "bidirectional"))
    )
    (net (code "80") (name "Net-(U1-VIN)") (class "Default")
      (node (ref "C10") (pin "1") (pinfunction "1_1") (pintype "passive"))
      (node (ref "J3") (pin "2") (pinfunction "2_2") (pintype "passive"))
      (node (ref "U1") (pin "2") (pinfunction "VIN_2") (pintype "power_in"))
    )
    (net (code "81") (name "Net-(U2-PA00(XIN32{slash}SER1:0{slash}TC2:0))") (class "Default")
      (node (ref "C8") (pin "2") (pinfunction "2_2") (pintype "passive"))
      (node (ref "U2") (pin "1") (pinfunction "PA00(XIN32/SER1:0/TC2:0)_1") (pintype "bidirectional"))
      (node (ref "Y1") (pin "P$1") (pinfunction "1_P$1") (pintype "passive"))
    )
    (net (code "82") (name "Net-(U2-PA01(XOUT32{slash}SER1:1{slash}TC2:1))") (class "Default")
      (node (ref "C7") (pin "2") (pinfunction "2_2") (pintype "passive"))
      (node (ref "U2") (pin "2") (pinfunction "PA01(XOUT32/SER1:1/TC2:1)_2") (pintype "bidirectional"))
      (node (ref "Y1") (pin "P$2") (pinfunction "2_P$2") (pintype "passive"))
    )
    (net (code "83") (name "unconnected-(J1-Pad3)") (class "Default")
      (node (ref "J1") (pin "3") (pinfunction "3_3") (pintype "bidirectional"))
    )
    (net (code "84") (name "unconnected-(J1-Pad4)") (class "Default")
      (node (ref "J1") (pin "4") (pinfunction "4_4") (pintype "bidirectional"))
    )
    (net (code "85") (name "unconnected-(J1-Pad7)") (class "Default")
      (node (ref "J1") (pin "7") (pinfunction "7_7") (pintype "bidirectional"))
    )
    (net (code "86") (name "unconnected-(J1-Pad8)") (class "Default")
      (node (ref "J1") (pin "8") (pinfunction "8_8") (pintype "bidirectional"))
    )
    (net (code "87") (name "unconnected-(J1-Pad9)") (class "Default")
      (node (ref "J1") (pin "9") (pinfunction "9_9") (pintype "bidirectional"))
    )
    (net (code "88") (name "unconnected-(J1-Pad10)") (class "Default")
      (node (ref "J1") (pin "10") (pinfunction "10_10") (pintype "bidirectional"))
    )
    (net (code "89") (name "unconnected-(J1-Pad11)") (class "Default")
      (node (ref "J1") (pin "11") (pinfunction "11_11") (pintype "bidirectional"))
    )
    (net (code "90") (name "unconnected-(J1-Pad12)") (class "Default")
      (node (ref "J1") (pin "12") (pinfunction "12_12") (pintype "bidirectional"))
    )
    (net (code "91") (name "unconnected-(J1-Pad13)") (class "Default")
      (node (ref "J1") (pin "13") (pinfunction "13_13") (pintype "bidirectional"))
    )
    (net (code "92") (name "unconnected-(J1-Pad14)") (class "Default")
      (node (ref "J1") (pin "14") (pinfunction "14_14") (pintype "bidirectional"))
    )
    (net (code "93") (name "unconnected-(J1-Pad15)") (class "Default")
      (node (ref "J1") (pin "15") (pinfunction "15_15") (pintype "bidirectional"))
    )
    (net (code "94") (name "unconnected-(J1-Pad16)") (class "Default")
      (node (ref "J1") (pin "16") (pinfunction "16_16") (pintype "bidirectional"))
    )
    (net (code "95") (name "unconnected-(J1-Pad17)") (class "Default")
      (node (ref "J1") (pin "17") (pinfunction "17_17") (pintype "bidirectional"))
    )
    (net (code "96") (name "unconnected-(J1-Pad18)") (class "Default")
      (node (ref "J1") (pin "18") (pinfunction "18_18") (pintype "bidirectional"))
    )
    (net (code "97") (name "unconnected-(J1-Pad19)") (class "Default")
      (node (ref "J1") (pin "19") (pinfunction "19_19") (pintype "bidirectional"))
    )
    (net (code "98") (name "unconnected-(J1-Pad20)") (class "Default")
      (node (ref "J1") (pin "20") (pinfunction "20_20") (pintype "bidirectional"))
    )
    (net (code "99") (name "unconnected-(J1-Pad23)") (class "Default")
      (node (ref "J1") (pin "23") (pinfunction "23_23") (pintype "bidirectional"))
    )
    (net (code "100") (name "unconnected-(J1-Pad24)") (class "Default")
      (node (ref "J1") (pin "24") (pinfunction "24_24") (pintype "bidirectional"))
    )
    (net (code "101") (name "unconnected-(J1-Pad25)") (class "Default")
      (node (ref "J1") (pin "25") (pinfunction "25_25") (pintype "bidirectional"))
    )
    (net (code "102") (name "unconnected-(J1-Pad26)") (class "Default")
      (node (ref "J1") (pin "26") (pinfunction "26_26") (pintype "bidirectional"))
    )
    (net (code "103") (name "unconnected-(J1-Pad27)") (class "Default")
      (node (ref "J1") (pin "27") (pinfunction "27_27") (pintype "bidirectional"))
    )
    (net (code "104") (name "unconnected-(J1-Pad28)") (class "Default")
      (node (ref "J1") (pin "28") (pinfunction "28_28") (pintype "bidirectional"))
    )
    (net (code "105") (name "unconnected-(J1-Pad29)") (class "Default")
      (node (ref "J1") (pin "29") (pinfunction "29_29") (pintype "bidirectional"))
    )
    (net (code "106") (name "unconnected-(J1-Pad30)") (class "Default")
      (node (ref "J1") (pin "30") (pinfunction "30_30") (pintype "bidirectional"))
    )
    (net (code "107") (name "unconnected-(J1-Pad31)") (class "Default")
      (node (ref "J1") (pin "31") (pinfunction "31_31") (pintype "bidirectional"))
    )
    (net (code "108") (name "unconnected-(J1-Pad32)") (class "Default")
      (node (ref "J1") (pin "32") (pinfunction "32_32") (pintype "bidirectional"))
    )
    (net (code "109") (name "unconnected-(J1-Pad33)") (class "Default")
      (node (ref "J1") (pin "33") (pinfunction "33_33") (pintype "bidirectional"))
    )
    (net (code "110") (name "unconnected-(J1-Pad34)") (class "Default")
      (node (ref "J1") (pin "34") (pinfunction "34_34") (pintype "bidirectional"))
    )
    (net (code "111") (name "unconnected-(J1-Pad35)") (class "Default")
      (node (ref "J1") (pin "35") (pinfunction "35_35") (pintype "bidirectional"))
    )
    (net (code "112") (name "unconnected-(J1-Pad36)") (class "Default")
      (node (ref "J1") (pin "36") (pinfunction "36_36") (pintype "bidirectional"))
    )
    (net (code "113") (name "unconnected-(J1-Pad37)") (class "Default")
      (node (ref "J1") (pin "37") (pinfunction "37_37") (pintype "bidirectional"))
    )
    (net (code "114") (name "unconnected-(J1-Pad38)") (class "Default")
      (node (ref "J1") (pin "38") (pinfunction "38_38") (pintype "bidirectional"))
    )
    (net (code "115") (name "unconnected-(J1-Pad39)") (class "Default")
      (node (ref "J1") (pin "39") (pinfunction "39_39") (pintype "bidirectional"))
    )
    (net (code "116") (name "unconnected-(J1-Pad40)") (class "Default")
      (node (ref "J1") (pin "40") (pinfunction "40_40") (pintype "bidirectional"))
    )
    (net (code "117") (name "unconnected-(J1-Pad41)") (class "Default")
      (node (ref "J1") (pin "41") (pinfunction "41_41") (pintype "bidirectional"))
    )
    (net (code "118") (name "unconnected-(J1-Pad42)") (class "Default")
      (node (ref "J1") (pin "42") (pinfunction "42_42") (pintype "bidirectional"))
    )
    (net (code "119") (name "unconnected-(J1-Pad43)") (class "Default")
      (node (ref "J1") (pin "43") (pinfunction "43_43") (pintype "bidirectional"))
    )
    (net (code "120") (name "unconnected-(J1-Pad44)") (class "Default")
      (node (ref "J1") (pin "44") (pinfunction "44_44") (pintype "bidirectional"))
    )
    (net (code "121") (name "unconnected-(J1-Pad45)") (class "Default")
      (node (ref "J1") (pin "45") (pinfunction "45_45") (pintype "bidirectional"))
    )
    (net (code "122") (name "unconnected-(J1-Pad46)") (class "Default")
      (node (ref "J1") (pin "46") (pinfunction "46_46") (pintype "bidirectional"))
    )
    (net (code "123") (name "unconnected-(J1-Pad47)") (class "Default")
      (node (ref "J1") (pin "47") (pinfunction "47_47") (pintype "bidirectional"))
    )
    (net (code "124") (name "unconnected-(J1-Pad48)") (class "Default")
      (node (ref "J1") (pin "48") (pinfunction "48_48") (pintype "bidirectional"))
    )
    (net (code "125") (name "unconnected-(J1-Pad49)") (class "Default")
      (node (ref "J1") (pin "49") (pinfunction "49_49") (pintype "bidirectional"))
    )
    (net (code "126") (name "unconnected-(J1-Pad50)") (class "Default")
      (node (ref "J1") (pin "50") (pinfunction "50_50") (pintype "bidirectional"))
    )
    (net (code "127") (name "unconnected-(J1-Pad51)") (class "Default")
      (node (ref "J1") (pin "51") (pinfunction "51_51") (pintype "bidirectional"))
    )
    (net (code "128") (name "unconnected-(J1-Pad53)") (class "Default")
      (node (ref "J1") (pin "53") (pinfunction "53_53") (pintype "bidirectional"))
    )
    (net (code "129") (name "unconnected-(J1-Pad54)") (class "Default")
      (node (ref "J1") (pin "54") (pinfunction "54_54") (pintype "bidirectional"))
    )
    (net (code "130") (name "unconnected-(J1-Pad55)") (class "Default")
      (node (ref "J1") (pin "55") (pinfunction "55_55") (pintype "bidirectional"))
    )
    (net (code "131") (name "unconnected-(J1-Pad56)") (class "Default")
      (node (ref "J1") (pin "56") (pinfunction "56_56") (pintype "bidirectional"))
    )
    (net (code "132") (name "unconnected-(J1-Pad57)") (class "Default")
      (node (ref "J1") (pin "57") (pinfunction "57_57") (pintype "bidirectional"))
    )
    (net (code "133") (name "unconnected-(J1-Pad58)") (class "Default")
      (node (ref "J1") (pin "58") (pinfunction "58_58") (pintype "bidirectional"))
    )
    (net (code "134") (name "unconnected-(J1-Pad59)") (class "Default")
      (node (ref "J1") (pin "59") (pinfunction "59_59") (pintype "bidirectional"))
    )
    (net (code "135") (name "unconnected-(J1-Pad60)") (class "Default")
      (node (ref "J1") (pin "60") (pinfunction "60_60") (pintype "bidirectional"))
    )
    (net (code "136") (name "unconnected-(J1-Pad61)") (class "Default")
      (node (ref "J1") (pin "61") (pinfunction "61_61") (pintype "bidirectional"))
    )
    (net (code "137") (name "unconnected-(J1-Pad62)") (class "Default")
      (node (ref "J1") (pin "62") (pinfunction "62_62") (pintype "bidirectional"))
    )
    (net (code "138") (name "unconnected-(J1-Pad63)") (class "Default")
      (node (ref "J1") (pin "63") (pinfunction "63_63") (pintype "bidirectional"))
    )
    (net (code "139") (name "unconnected-(J1-Pad64)") (class "Default")
      (node (ref "J1") (pin "64") (pinfunction "64_64") (pintype "bidirectional"))
    )
    (net (code "140") (name "unconnected-(J1-Pad66)") (class "Default")
      (node (ref "J1") (pin "66") (pinfunction "66_66") (pintype "bidirectional"))
    )
    (net (code "141") (name "unconnected-(J1-Pad68)") (class "Default")
      (node (ref "J1") (pin "68") (pinfunction "68_68") (pintype "bidirectional"))
    )
    (net (code "142") (name "unconnected-(J1-Pad69)") (class "Default")
      (node (ref "J1") (pin "69") (pinfunction "69_69") (pintype "bidirectional"))
    )
    (net (code "143") (name "unconnected-(J1-Pad70)") (class "Default")
      (node (ref "J1") (pin "70") (pinfunction "70_70") (pintype "bidirectional"))
    )
    (net (code "144") (name "unconnected-(J1-Pad71)") (class "Default")
      (node (ref "J1") (pin "71") (pinfunction "71_71") (pintype "bidirectional"))
    )
    (net (code "145") (name "unconnected-(J1-Pad72)") (class "Default")
      (node (ref "J1") (pin "72") (pinfunction "72_72") (pintype "bidirectional"))
    )
    (net (code "146") (name "unconnected-(J1-Pad73)") (class "Default")
      (node (ref "J1") (pin "73") (pinfunction "73_73") (pintype "bidirectional"))
    )
    (net (code "147") (name "unconnected-(J1-Pad74)") (class "Default")
      (node (ref "J1") (pin "74") (pinfunction "74_74") (pintype "bidirectional"))
    )
    (net (code "148") (name "unconnected-(J1-Pad76)") (class "Default")
      (node (ref "J1") (pin "76") (pinfunction "76_76") (pintype "bidirectional"))
    )
    (net (code "149") (name "unconnected-(J1-Pad77)") (class "Default")
      (node (ref "J1") (pin "77") (pinfunction "77_77") (pintype "bidirectional"))
    )
    (net (code "150") (name "unconnected-(J1-Pad78)") (class "Default")
      (node (ref "J1") (pin "78") (pinfunction "78_78") (pintype "bidirectional"))
    )
    (net (code "151") (name "unconnected-(J1-Pad79)") (class "Default")
      (node (ref "J1") (pin "79") (pinfunction "79_79") (pintype "bidirectional"))
    )
    (net (code "152") (name "unconnected-(J1-Pad80)") (class "Default")
      (node (ref "J1") (pin "80") (pinfunction "80_80") (pintype "bidirectional"))
    )
    (net (code "153") (name "unconnected-(J1-Pad81)") (class "Default")
      (node (ref "J1") (pin "81") (pinfunction "81_81") (pintype "bidirectional"))
    )
    (net (code "154") (name "unconnected-(J1-Pad82)") (class "Default")
      (node (ref "J1") (pin "82") (pinfunction "82_82") (pintype "bidirectional"))
    )
    (net (code "155") (name "unconnected-(J1-Pad83)") (class "Default")
      (node (ref "J1") (pin "83") (pinfunction "83_83") (pintype "bidirectional"))
    )
    (net (code "156") (name "unconnected-(J1-Pad84)") (class "Default")
      (node (ref "J1") (pin "84") (pinfunction "84_84") (pintype "bidirectional"))
    )
    (net (code "157") (name "unconnected-(J1-Pad85)") (class "Default")
      (node (ref "J1") (pin "85") (pinfunction "85_85") (pintype "bidirectional"))
    )
    (net (code "158") (name "unconnected-(J1-Pad86)") (class "Default")
      (node (ref "J1") (pin "86") (pinfunction "86_86") (pintype "bidirectional"))
    )
    (net (code "159") (name "unconnected-(J1-Pad87)") (class "Default")
      (node (ref "J1") (pin "87") (pinfunction "87_87") (pintype "bidirectional"))
    )
    (net (code "160") (name "unconnected-(J1-Pad88)") (class "Default")
      (node (ref "J1") (pin "88") (pinfunction "88_88") (pintype "bidirectional"))
    )
    (net (code "161") (name "unconnected-(J1-Pad89)") (class "Default")
      (node (ref "J1") (pin "89") (pinfunction "89_89") (pintype "bidirectional"))
    )
    (net (code "162") (name "unconnected-(J1-Pad90)") (class "Default")
      (node (ref "J1") (pin "90") (pinfunction "90_90") (pintype "bidirectional"))
    )
    (net (code "163") (name "unconnected-(J1-Pad92)") (class "Default")
      (node (ref "J1") (pin "92") (pinfunction "92_92") (pintype "bidirectional"))
    )
    (net (code "164") (name "unconnected-(J1-Pad95)") (class "Default")
      (node (ref "J1") (pin "95") (pinfunction "95_95") (pintype "bidirectional"))
    )
    (net (code "165") (name "unconnected-(J1-Pad96)") (class "Default")
      (node (ref "J1") (pin "96") (pinfunction "96_96") (pintype "bidirectional"))
    )
    (net (code "166") (name "unconnected-(J1-Pad97)") (class "Default")
      (node (ref "J1") (pin "97") (pinfunction "97_97") (pintype "bidirectional"))
    )
    (net (code "167") (name "unconnected-(J1-Pad98)") (class "Default")
      (node (ref "J1") (pin "98") (pinfunction "98_98") (pintype "bidirectional"))
    )
    (net (code "168") (name "unconnected-(J1-Pad99)") (class "Default")
      (node (ref "J1") (pin "99") (pinfunction "99_99") (pintype "bidirectional"))
    )
    (net (code "169") (name "unconnected-(J1-Pad100)") (class "Default")
      (node (ref "J1") (pin "100") (pinfunction "100_100") (pintype "bidirectional"))
    )
    (net (code "170") (name "unconnected-(J1-Pad102)") (class "Default")
      (node (ref "J1") (pin "102") (pinfunction "102_102") (pintype "bidirectional"))
    )
    (net (code "171") (name "unconnected-(J1-Pad103)") (class "Default")
      (node (ref "J1") (pin "103") (pinfunction "103_103") (pintype "bidirectional"))
    )
    (net (code "172") (name "unconnected-(J1-Pad104)") (class "Default")
      (node (ref "J1") (pin "104") (pinfunction "104_104") (pintype "bidirectional"))
    )
    (net (code "173") (name "unconnected-(J10-Pad2)") (class "Default")
      (node (ref "J10") (pin "2") (pinfunction "2_2") (pintype "passive"))
    )
    (net (code "174") (name "unconnected-(J11-Pad1)") (class "Default")
      (node (ref "J11") (pin "1") (pinfunction "1_1") (pintype "passive"))
    )
    (net (code "175") (name "unconnected-(S1-O-Pad1)") (class "Default")
      (node (ref "S1") (pin "1") (pinfunction "O_1") (pintype "passive"))
    )
    (net (code "176") (name "unconnected-(S2-O-Pad1)") (class "Default")
      (node (ref "S2") (pin "1") (pinfunction "O_1") (pintype "passive"))
    )
    (net (code "177") (name "unconnected-(U$4-EN-Pad6)") (class "Default")
      (node (ref "U$4") (pin "6") (pinfunction "EN_6") (pintype "bidirectional"))
    )
    (net (code "178") (name "unconnected-(U$4-STATE-Pad1)") (class "Default")
      (node (ref "U$4") (pin "1") (pinfunction "STATE_1") (pintype "bidirectional"))
    )
    (net (code "179") (name "unconnected-(U2-PA03(AIN1{slash}REFA)-Pad4)") (class "Default")
      (node (ref "U2") (pin "4") (pinfunction "PA03(AIN1/REFA)_4") (pintype "bidirectional"))
    )
    (net (code "180") (name "unconnected-(U2-PA04(AIN4{slash}REFB{slash}SER0:0{slash}TC0:0)-Pad9)") (class "Default")
      (node (ref "U2") (pin "9") (pinfunction "PA04(AIN4/REFB/SER0:0/TC0:0)_9") (pintype "bidirectional"))
    )
    (net (code "181") (name "unconnected-(U2-PA05(AIN5{slash}SER0:1{slash}TC0:1)-Pad10)") (class "Default")
      (node (ref "U2") (pin "10") (pinfunction "PA05(AIN5/SER0:1/TC0:1)_10") (pintype "bidirectional"))
    )
    (net (code "182") (name "unconnected-(U2-PA06(AIN6{slash}SER0:2{slash}TC1:0)-Pad11)") (class "Default")
      (node (ref "U2") (pin "11") (pinfunction "PA06(AIN6/SER0:2/TC1:0)_11") (pintype "bidirectional"))
    )
    (net (code "183") (name "unconnected-(U2-PA07(AIN7{slash}SER0:3{slash}TC1:1)-Pad12)") (class "Default")
      (node (ref "U2") (pin "12") (pinfunction "PA07(AIN7/SER0:3/TC1:1)_12") (pintype "bidirectional"))
    )
    (net (code "184") (name "unconnected-(U2-PA10(AIN18{slash}SER0:2+)-Pad15)") (class "Default")
      (node (ref "U2") (pin "15") (pinfunction "PA10(AIN18/SER0:2+)_15") (pintype "bidirectional"))
    )
    (net (code "185") (name "unconnected-(U2-PA11(AIN19{slash}SER0:3+)-Pad16)") (class "Default")
      (node (ref "U2") (pin "16") (pinfunction "PA11(AIN19/SER0:3+)_16") (pintype "bidirectional"))
    )
    (net (code "186") (name "unconnected-(U2-PA12(I2C{slash}SER2:0+)-Pad21)") (class "Default")
      (node (ref "U2") (pin "21") (pinfunction "PA12(I2C/SER2:0+)_21") (pintype "bidirectional"))
    )
    (net (code "187") (name "unconnected-(U2-PA13(I2C{slash}SER2:1+)-Pad22)") (class "Default")
      (node (ref "U2") (pin "22") (pinfunction "PA13(I2C/SER2:1+)_22") (pintype "bidirectional"))
    )
    (net (code "188") (name "unconnected-(U2-PA14(XIN{slash}SER2:2+)-Pad23)") (class "Default")
      (node (ref "U2") (pin "23") (pinfunction "PA14(XIN/SER2:2+)_23") (pintype "bidirectional"))
    )
    (net (code "189") (name "unconnected-(U2-PA15(XOUT{slash}SER2:3+)-Pad24)") (class "Default")
      (node (ref "U2") (pin "24") (pinfunction "PA15(XOUT/SER2:3+)_24") (pintype "bidirectional"))
    )
    (net (code "190") (name "unconnected-(U2-PA18(SER1:2+)-Pad27)") (class "Default")
      (node (ref "U2") (pin "27") (pinfunction "PA18(SER1:2+)_27") (pintype "bidirectional"))
    )
    (net (code "191") (name "unconnected-(U2-PA19(SER1:3+)-Pad28)") (class "Default")
      (node (ref "U2") (pin "28") (pinfunction "PA19(SER1:3+)_28") (pintype "bidirectional"))
    )
    (net (code "192") (name "unconnected-(U2-PA20(SER5:2+)-Pad29)") (class "Default")
      (node (ref "U2") (pin "29") (pinfunction "PA20(SER5:2+)_29") (pintype "bidirectional"))
    )
    (net (code "193") (name "unconnected-(U2-PA21(SER5:3+)-Pad30)") (class "Default")
      (node (ref "U2") (pin "30") (pinfunction "PA21(SER5:3+)_30") (pintype "bidirectional"))
    )
    (net (code "194") (name "unconnected-(U2-PA27-Pad39)") (class "Default")
      (node (ref "U2") (pin "39") (pinfunction "PA27_39") (pintype "bidirectional"))
    )
    (net (code "195") (name "unconnected-(U2-PB02(AIN10{slash}SER5:0)-Pad47)") (class "Default")
      (node (ref "U2") (pin "47") (pinfunction "PB02(AIN10/SER5:0)_47") (pintype "bidirectional"))
    )
    (net (code "196") (name "unconnected-(U2-PB03(AIN11{slash}SER5:1)-Pad48)") (class "Default")
      (node (ref "U2") (pin "48") (pinfunction "PB03(AIN11/SER5:1)_48") (pintype "bidirectional"))
    )
    (net (code "197") (name "unconnected-(U2-PB08(AIN2{slash}SER4:0{slash}TC4:0)-Pad7)") (class "Default")
      (node (ref "U2") (pin "7") (pinfunction "PB08(AIN2/SER4:0/TC4:0)_7") (pintype "bidirectional"))
    )
    (net (code "198") (name "unconnected-(U2-PB09(AIN3{slash}SER4:1{slash}TC4:1)-Pad8)") (class "Default")
      (node (ref "U2") (pin "8") (pinfunction "PB09(AIN3/SER4:1/TC4:1)_8") (pintype "bidirectional"))
    )
    (net (code "199") (name "unconnected-(U2-PB10(SER4:2+)-Pad19)") (class "Default")
      (node (ref "U2") (pin "19") (pinfunction "PB10(SER4:2+)_19") (pintype "bidirectional"))
    )
    (net (code "200") (name "unconnected-(U2-PB11(SER4:3+)-Pad20)") (class "Default")
      (node (ref "U2") (pin "20") (pinfunction "PB11(SER4:3+)_20") (pintype "bidirectional"))
    )
    (net (code "201") (name "unconnected-(U2-PB22(SER5:2+)-Pad37)") (class "Default")
      (node (ref "U2") (pin "37") (pinfunction "PB22(SER5:2+)_37") (pintype "bidirectional"))
    )
    (net (code "202") (name "unconnected-(U2-PB23(SER5:3+)-Pad38)") (class "Default")
      (node (ref "U2") (pin "38") (pinfunction "PB23(SER5:3+)_38") (pintype "bidirectional"))
    )
    (net (code "203") (name "unconnected-(U2-VDDIO-Pad17)") (class "Default")
      (node (ref "U2") (pin "17") (pinfunction "VDDIO_17") (pintype "bidirectional"))
    )
    (net (code "204") (name "unconnected-(U2-VDDIO-Pad36)") (class "Default")
      (node (ref "U2") (pin "36") (pinfunction "VDDIO_36") (pintype "bidirectional"))
    )
  )
)
